# CANoPi.net
KiCad netlist of a schematic drawn in EAGLE
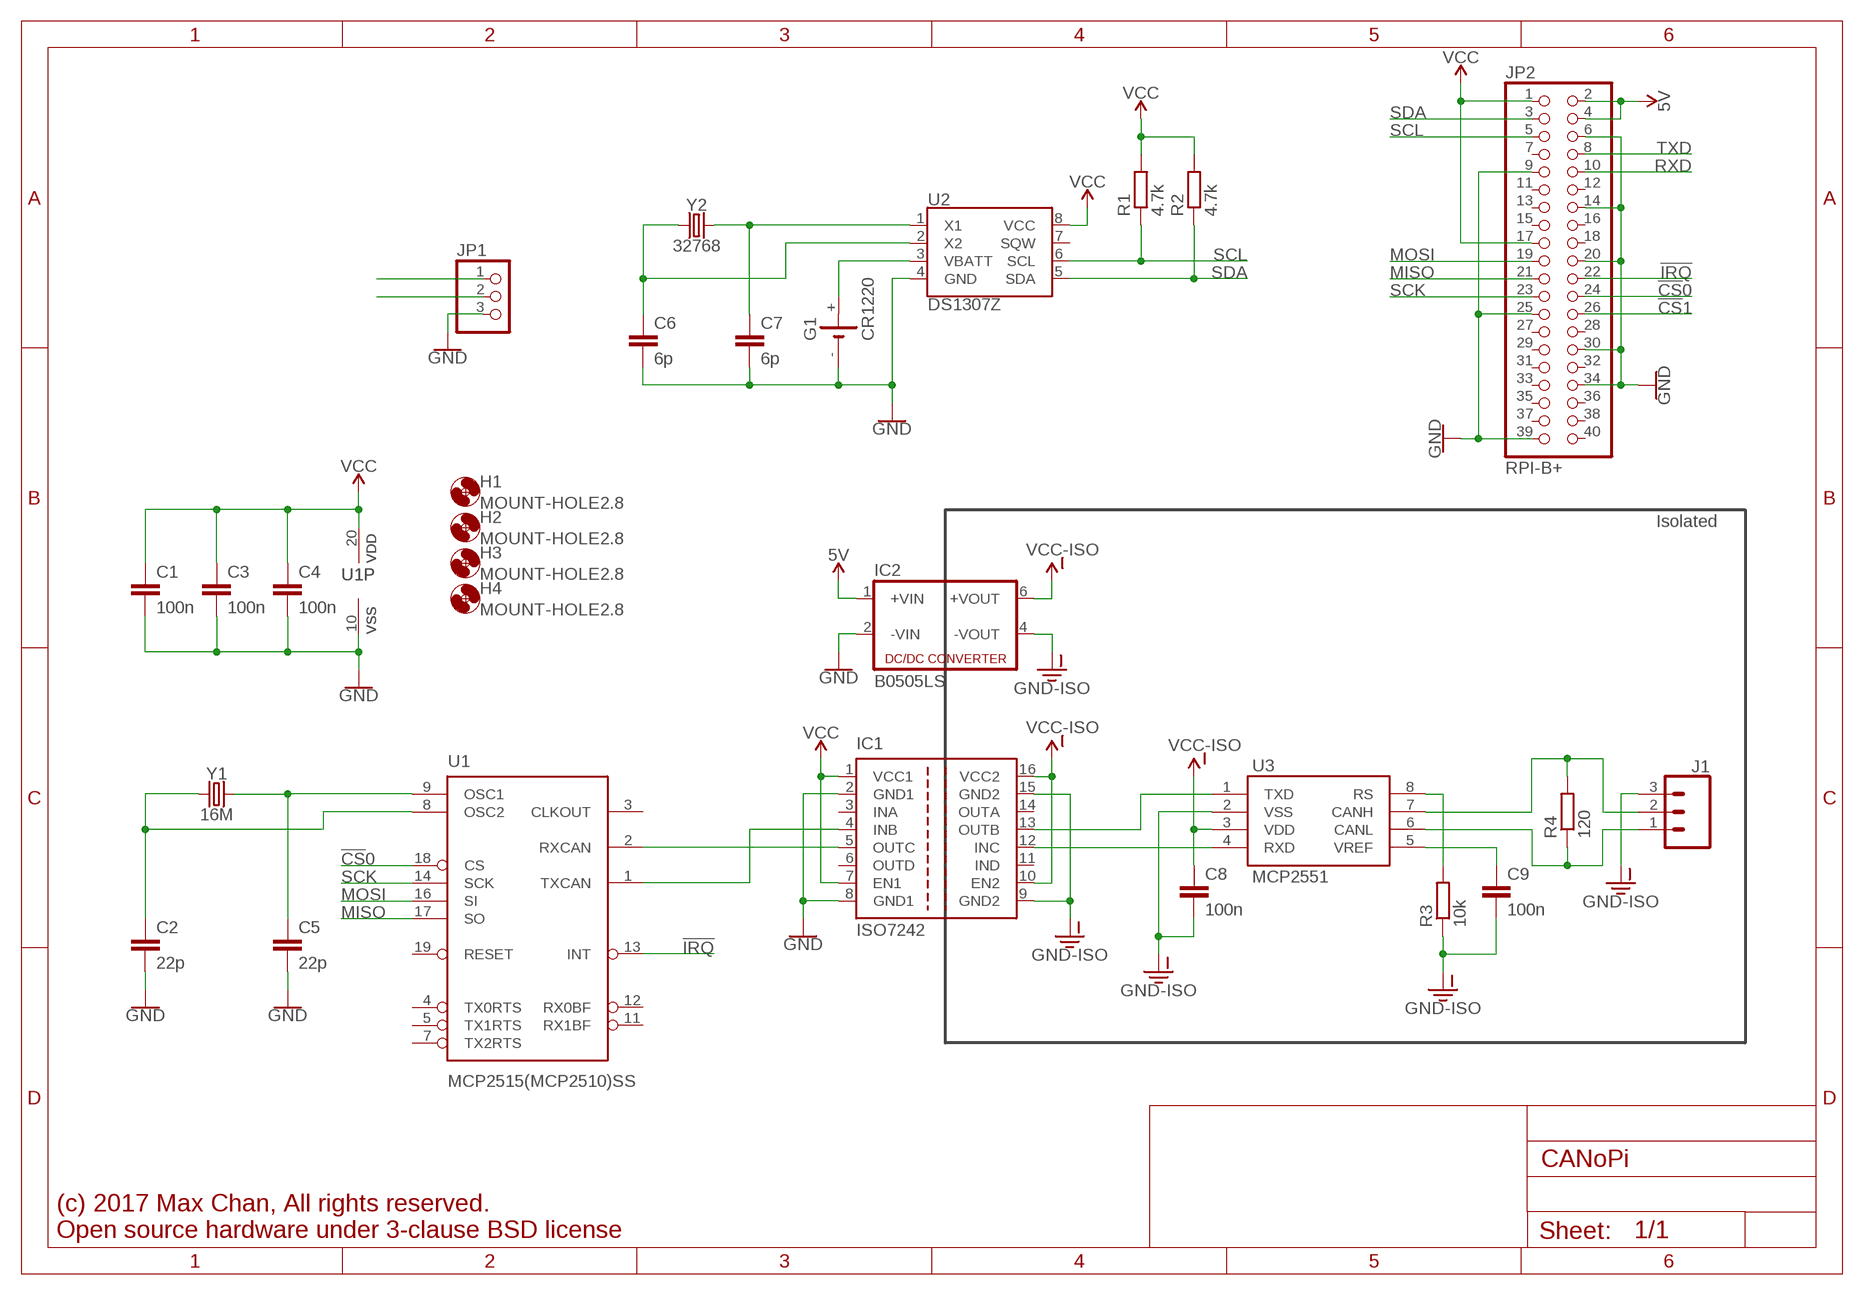
[diagram p0: schematic, sheet 1]

(export (version "E")
  (design (tool "Eeschema 10.0.6"))
  (components
    (comp (ref "C1")
      (value "100n")
      (footprint "eagle-import:C0603")
      (libsource (lib "eagle-import") (part "C-EUC0603"))
    )
    (comp (ref "C2")
      (value "22p")
      (footprint "eagle-import:C0603")
      (libsource (lib "eagle-import") (part "C-EUC0603"))
    )
    (comp (ref "C3")
      (value "100n")
      (footprint "eagle-import:C0603")
      (libsource (lib "eagle-import") (part "C-EUC0603"))
    )
    (comp (ref "C4")
      (value "100n")
      (footprint "eagle-import:C0603")
      (libsource (lib "eagle-import") (part "C-EUC0603"))
    )
    (comp (ref "C5")
      (value "22p")
      (footprint "eagle-import:C0603")
      (libsource (lib "eagle-import") (part "C-EUC0603"))
    )
    (comp (ref "C6")
      (value "6p")
      (footprint "eagle-import:C0603")
      (libsource (lib "eagle-import") (part "C-EUC0603"))
    )
    (comp (ref "C7")
      (value "6p")
      (footprint "eagle-import:C0603")
      (libsource (lib "eagle-import") (part "C-EUC0603"))
    )
    (comp (ref "C8")
      (value "100n")
      (footprint "eagle-import:C0603")
      (libsource (lib "eagle-import") (part "C-EUC0603"))
    )
    (comp (ref "C9")
      (value "100n")
      (footprint "eagle-import:C0603")
      (libsource (lib "eagle-import") (part "C-EUC0603"))
    )
    (comp (ref "G1")
      (value "CR1220")
      (footprint "eagle-import:CH291-1220LF")
      (libsource (lib "eagle-import") (part "CH291-1220LF"))
    )
    (comp (ref "H1")
      (value "MOUNT-HOLE2.8")
      (footprint "eagle-import:2,8")
      (libsource (lib "eagle-import") (part "MOUNT-HOLE2.8"))
    )
    (comp (ref "H2")
      (value "MOUNT-HOLE2.8")
      (footprint "eagle-import:2,8")
      (libsource (lib "eagle-import") (part "MOUNT-HOLE2.8"))
    )
    (comp (ref "H3")
      (value "MOUNT-HOLE2.8")
      (footprint "eagle-import:2,8")
      (libsource (lib "eagle-import") (part "MOUNT-HOLE2.8"))
    )
    (comp (ref "H4")
      (value "MOUNT-HOLE2.8")
      (footprint "eagle-import:2,8")
      (libsource (lib "eagle-import") (part "MOUNT-HOLE2.8"))
    )
    (comp (ref "IC1")
      (value "ISO7242")
      (footprint "eagle-import:SO-16DW")
      (fields (field (name "MPN") "ISO7242MDW"))
      (libsource (lib "eagle-import") (part "ISO7242"))
    )
    (comp (ref "IC2")
      (value "B0505LS")
      (footprint "eagle-import:NMA-SINGLE")
      (libsource (lib "eagle-import") (part "NMA-SINGLE"))
    )
    (comp (ref "J1")
      (value "CONN_03SCREW")
      (footprint "eagle-import:SCREWTERMINAL-3.5MM-3")
      (libsource (lib "eagle-import") (part "CONN_03SCREW"))
    )
    (comp (ref "JP1")
      (value "PINHD-1X3/90")
      (footprint "eagle-import:1X03_90")
      (libsource (lib "eagle-import") (part "PINHD-1X3/90"))
    )
    (comp (ref "JP2")
      (value "RPI-B+")
      (footprint "eagle-import:2X20")
      (libsource (lib "eagle-import") (part "PINHD-2X20"))
    )
    (comp (ref "R1")
      (value "4.7k")
      (footprint "eagle-import:R0603")
      (libsource (lib "eagle-import") (part "R-EU_R0603"))
    )
    (comp (ref "R2")
      (value "4.7k")
      (footprint "eagle-import:R0603")
      (libsource (lib "eagle-import") (part "R-EU_R0603"))
    )
    (comp (ref "R3")
      (value "10k")
      (footprint "eagle-import:R0603")
      (libsource (lib "eagle-import") (part "R-EU_R0603"))
    )
    (comp (ref "R4")
      (value "120")
      (footprint "eagle-import:R0603")
      (libsource (lib "eagle-import") (part "R-EU_R0603"))
    )
    (comp (ref "U1")
      (value "MCP2515(MCP2510)SS")
      (footprint "eagle-import:SSOP20")
      (libsource (lib "eagle-import") (part "MCP2515(MCP2510)SS"))
    )
    (comp (ref "U2")
      (value "DS1307Z")
      (footprint "eagle-import:SO08-0.15")
      (libsource (lib "eagle-import") (part "DS1307Z"))
    )
    (comp (ref "U3")
      (value "MCP2551")
      (footprint "eagle-import:SO08")
      (libsource (lib "eagle-import") (part "MCP2551"))
    )
    (comp (ref "Y1")
      (value "16M")
      (footprint "eagle-import:CRYSTAL-SMD-5X3.2-4PAD")
      (libsource (lib "eagle-import") (part "CRYSTALSMD-5X3.2-4PAD"))
    )
    (comp (ref "Y2")
      (value "32768")
      (footprint "eagle-import:CRYSTAL-SMD-3.2X1.5MM")
      (libsource (lib "eagle-import") (part "CRYSTALSMD-3.2X1.5"))
    )
  )
  (nets
    (net (code "1") (name "/MISO") (class "Default")
      (node (ref "JP2") (pin "21") (pinfunction "21_21") (pintype "passive"))
      (node (ref "U1") (pin "17") (pinfunction "SO_17") (pintype "output"))
    )
    (net (code "2") (name "/MOSI") (class "Default")
      (node (ref "JP2") (pin "19") (pinfunction "19_19") (pintype "passive"))
      (node (ref "U1") (pin "16") (pinfunction "SI_16") (pintype "input"))
    )
    (net (code "3") (name "/RXD") (class "Default")
      (node (ref "JP1") (pin "1") (pinfunction "1_1") (pintype "passive"))
      (node (ref "JP2") (pin "10") (pinfunction "10_10") (pintype "passive"))
    )
    (net (code "4") (name "/SCK") (class "Default")
      (node (ref "JP2") (pin "23") (pinfunction "23_23") (pintype "passive"))
      (node (ref "U1") (pin "14") (pinfunction "SCK_14") (pintype "input"))
    )
    (net (code "5") (name "/SCL") (class "Default")
      (node (ref "JP2") (pin "5") (pinfunction "5_5") (pintype "passive"))
      (node (ref "R1") (pin "1") (pinfunction "1_1") (pintype "passive"))
      (node (ref "U2") (pin "6") (pinfunction "SCL_6") (pintype "bidirectional"))
    )
    (net (code "6") (name "/SDA") (class "Default")
      (node (ref "JP2") (pin "3") (pinfunction "3_3") (pintype "passive"))
      (node (ref "R2") (pin "1") (pinfunction "1_1") (pintype "passive"))
      (node (ref "U2") (pin "5") (pinfunction "SDA_5") (pintype "bidirectional"))
    )
    (net (code "7") (name "/TXD") (class "Default")
      (node (ref "JP1") (pin "2") (pinfunction "2_2") (pintype "passive"))
      (node (ref "JP2") (pin "8") (pinfunction "8_8") (pintype "passive"))
    )
    (net (code "8") (name "/~{CS}0") (class "Default")
      (node (ref "JP2") (pin "24") (pinfunction "24_24") (pintype "passive"))
      (node (ref "U1") (pin "18") (pinfunction "CS_18") (pintype "input"))
    )
    (net (code "9") (name "/~{CS}1") (class "Default")
      (node (ref "JP2") (pin "26") (pinfunction "26_26") (pintype "passive"))
    )
    (net (code "10") (name "/~{IRQ}") (class "Default")
      (node (ref "JP2") (pin "22") (pinfunction "22_22") (pintype "passive"))
      (node (ref "U1") (pin "13") (pinfunction "INT_13") (pintype "output"))
    )
    (net (code "11") (name "5V") (class "Default")
      (node (ref "IC2") (pin "1") (pinfunction "+VIN_1") (pintype "passive"))
      (node (ref "JP2") (pin "2") (pinfunction "2_2") (pintype "passive"))
      (node (ref "JP2") (pin "4") (pinfunction "4_4") (pintype "passive"))
    )
    (net (code "12") (name "GND") (class "Default")
      (node (ref "C1") (pin "2") (pinfunction "2_2") (pintype "passive"))
      (node (ref "C2") (pin "2") (pinfunction "2_2") (pintype "passive"))
      (node (ref "C3") (pin "2") (pinfunction "2_2") (pintype "passive"))
      (node (ref "C4") (pin "2") (pinfunction "2_2") (pintype "passive"))
      (node (ref "C5") (pin "2") (pinfunction "2_2") (pintype "passive"))
      (node (ref "C6") (pin "2") (pinfunction "2_2") (pintype "passive"))
      (node (ref "C7") (pin "2") (pinfunction "2_2") (pintype "passive"))
      (node (ref "G1") (pin "-") (pinfunction "-_-") (pintype "passive"))
      (node (ref "IC1") (pin "2") (pinfunction "GND1_2") (pintype "power_in"))
      (node (ref "IC1") (pin "8") (pinfunction "GND1_8") (pintype "power_in"))
      (node (ref "IC2") (pin "2") (pinfunction "-VIN_2") (pintype "passive"))
      (node (ref "JP1") (pin "3") (pinfunction "3_3") (pintype "passive"))
      (node (ref "JP2") (pin "14") (pinfunction "14_14") (pintype "passive"))
      (node (ref "JP2") (pin "20") (pinfunction "20_20") (pintype "passive"))
      (node (ref "JP2") (pin "25") (pinfunction "25_25") (pintype "passive"))
      (node (ref "JP2") (pin "30") (pinfunction "30_30") (pintype "passive"))
      (node (ref "JP2") (pin "34") (pinfunction "34_34") (pintype "passive"))
      (node (ref "JP2") (pin "39") (pinfunction "39_39") (pintype "passive"))
      (node (ref "JP2") (pin "6") (pinfunction "6_6") (pintype "passive"))
      (node (ref "JP2") (pin "9") (pinfunction "9_9") (pintype "passive"))
      (node (ref "U1") (pin "10") (pinfunction "VSS_10") (pintype "power_in"))
      (node (ref "U2") (pin "4") (pinfunction "GND_4") (pintype "bidirectional"))
    )
    (net (code "13") (name "GND-ISO") (class "Default")
      (node (ref "C8") (pin "2") (pinfunction "2_2") (pintype "passive"))
      (node (ref "C9") (pin "2") (pinfunction "2_2") (pintype "passive"))
      (node (ref "IC1") (pin "15") (pinfunction "GND2_15") (pintype "power_in"))
      (node (ref "IC1") (pin "9") (pinfunction "GND2_9") (pintype "power_in"))
      (node (ref "IC2") (pin "4") (pinfunction "-VOUT_4") (pintype "passive"))
      (node (ref "J1") (pin "3") (pinfunction "3_3") (pintype "passive"))
      (node (ref "R3") (pin "1") (pinfunction "1_1") (pintype "passive"))
      (node (ref "U3") (pin "2") (pinfunction "VSS_2") (pintype "bidirectional"))
    )
    (net (code "14") (name "Net-(IC1-INB)") (class "Default")
      (node (ref "IC1") (pin "4") (pinfunction "INB_4") (pintype "input"))
      (node (ref "U1") (pin "1") (pinfunction "TXCAN_1") (pintype "output"))
    )
    (net (code "15") (name "Net-(IC1-INC)") (class "Default")
      (node (ref "IC1") (pin "12") (pinfunction "INC_12") (pintype "input"))
      (node (ref "U3") (pin "4") (pinfunction "RXD_4") (pintype "bidirectional"))
    )
    (net (code "16") (name "Net-(IC1-OUTB)") (class "Default")
      (node (ref "IC1") (pin "13") (pinfunction "OUTB_13") (pintype "output"))
      (node (ref "U3") (pin "1") (pinfunction "TXD_1") (pintype "bidirectional"))
    )
    (net (code "17") (name "Net-(IC1-OUTC)") (class "Default")
      (node (ref "IC1") (pin "5") (pinfunction "OUTC_5") (pintype "output"))
      (node (ref "U1") (pin "2") (pinfunction "RXCAN_2") (pintype "input"))
    )
    (net (code "18") (name "Net-(U1A-OSC1)") (class "Default")
      (node (ref "C5") (pin "1") (pinfunction "1_1") (pintype "passive"))
      (node (ref "U1") (pin "9") (pinfunction "OSC1_9") (pintype "input"))
      (node (ref "Y1") (pin "3") (pinfunction "2_3") (pintype "passive"))
    )
    (net (code "19") (name "Net-(U1A-OSC2)") (class "Default")
      (node (ref "C2") (pin "1") (pinfunction "1_1") (pintype "passive"))
      (node (ref "U1") (pin "8") (pinfunction "OSC2_8") (pintype "output"))
      (node (ref "Y1") (pin "1") (pinfunction "1_1") (pintype "passive"))
    )
    (net (code "20") (name "Net-(U2-VBATT)") (class "Default")
      (node (ref "G1") (pin "+") (pinfunction "+_+") (pintype "passive"))
      (node (ref "U2") (pin "3") (pinfunction "VBATT_3") (pintype "bidirectional"))
    )
    (net (code "21") (name "Net-(U2-X1)") (class "Default")
      (node (ref "C7") (pin "1") (pinfunction "1_1") (pintype "passive"))
      (node (ref "U2") (pin "1") (pinfunction "X1_1") (pintype "bidirectional"))
      (node (ref "Y2") (pin "P$2") (pinfunction "2_P$2") (pintype "passive"))
    )
    (net (code "22") (name "Net-(U2-X2)") (class "Default")
      (node (ref "C6") (pin "1") (pinfunction "1_1") (pintype "passive"))
      (node (ref "U2") (pin "2") (pinfunction "X2_2") (pintype "bidirectional"))
      (node (ref "Y2") (pin "P$1") (pinfunction "1_P$1") (pintype "passive"))
    )
    (net (code "23") (name "Net-(U3-CANH)") (class "Default")
      (node (ref "J1") (pin "2") (pinfunction "2_2") (pintype "passive"))
      (node (ref "R4") (pin "2") (pinfunction "2_2") (pintype "passive"))
      (node (ref "U3") (pin "7") (pinfunction "CANH_7") (pintype "bidirectional"))
    )
    (net (code "24") (name "Net-(U3-CANL)") (class "Default")
      (node (ref "J1") (pin "1") (pinfunction "1_1") (pintype "passive"))
      (node (ref "R4") (pin "1") (pinfunction "1_1") (pintype "passive"))
      (node (ref "U3") (pin "6") (pinfunction "CANL_6") (pintype "bidirectional"))
    )
    (net (code "25") (name "Net-(U3-RS)") (class "Default")
      (node (ref "R3") (pin "2") (pinfunction "2_2") (pintype "passive"))
      (node (ref "U3") (pin "8") (pinfunction "RS_8") (pintype "bidirectional"))
    )
    (net (code "26") (name "Net-(U3-VREF)") (class "Default")
      (node (ref "C9") (pin "1") (pinfunction "1_1") (pintype "passive"))
      (node (ref "U3") (pin "5") (pinfunction "VREF_5") (pintype "bidirectional"))
    )
    (net (code "27") (name "VCC") (class "Default")
      (node (ref "C1") (pin "1") (pinfunction "1_1") (pintype "passive"))
      (node (ref "C3") (pin "1") (pinfunction "1_1") (pintype "passive"))
      (node (ref "C4") (pin "1") (pinfunction "1_1") (pintype "passive"))
      (node (ref "IC1") (pin "1") (pinfunction "VCC1_1") (pintype "power_in"))
      (node (ref "IC1") (pin "7") (pinfunction "EN1_7") (pintype "input"))
      (node (ref "JP2") (pin "1") (pinfunction "1_1") (pintype "passive"))
      (node (ref "JP2") (pin "17") (pinfunction "17_17") (pintype "passive"))
      (node (ref "R1") (pin "2") (pinfunction "2_2") (pintype "passive"))
      (node (ref "R2") (pin "2") (pinfunction "2_2") (pintype "passive"))
      (node (ref "U1") (pin "20") (pinfunction "VDD_20") (pintype "power_in"))
      (node (ref "U2") (pin "8") (pinfunction "VCC_8") (pintype "bidirectional"))
    )
    (net (code "28") (name "VCC-ISO") (class "Default")
      (node (ref "C8") (pin "1") (pinfunction "1_1") (pintype "passive"))
      (node (ref "IC1") (pin "10") (pinfunction "EN2_10") (pintype "input"))
      (node (ref "IC1") (pin "16") (pinfunction "VCC2_16") (pintype "power_in"))
      (node (ref "IC2") (pin "6") (pinfunction "+VOUT_6") (pintype "passive"))
      (node (ref "U3") (pin "3") (pinfunction "VDD_3") (pintype "bidirectional"))
    )
    (net (code "29") (name "unconnected-(IC1-INA-Pad3)") (class "Default")
      (node (ref "IC1") (pin "3") (pinfunction "INA_3") (pintype "input"))
    )
    (net (code "30") (name "unconnected-(IC1-IND-Pad11)") (class "Default")
      (node (ref "IC1") (pin "11") (pinfunction "IND_11") (pintype "input"))
    )
    (net (code "31") (name "unconnected-(IC1-OUTA-Pad14)") (class "Default")
      (node (ref "IC1") (pin "14") (pinfunction "OUTA_14") (pintype "output"))
    )
    (net (code "32") (name "unconnected-(IC1-OUTD-Pad6)") (class "Default")
      (node (ref "IC1") (pin "6") (pinfunction "OUTD_6") (pintype "output"))
    )
    (net (code "33") (name "unconnected-(JP2-Pad7)") (class "Default")
      (node (ref "JP2") (pin "7") (pinfunction "7_7") (pintype "passive"))
    )
    (net (code "34") (name "unconnected-(JP2-Pad11)") (class "Default")
      (node (ref "JP2") (pin "11") (pinfunction "11_11") (pintype "passive"))
    )
    (net (code "35") (name "unconnected-(JP2-Pad12)") (class "Default")
      (node (ref "JP2") (pin "12") (pinfunction "12_12") (pintype "passive"))
    )
    (net (code "36") (name "unconnected-(JP2-Pad13)") (class "Default")
      (node (ref "JP2") (pin "13") (pinfunction "13_13") (pintype "passive"))
    )
    (net (code "37") (name "unconnected-(JP2-Pad15)") (class "Default")
      (node (ref "JP2") (pin "15") (pinfunction "15_15") (pintype "passive"))
    )
    (net (code "38") (name "unconnected-(JP2-Pad16)") (class "Default")
      (node (ref "JP2") (pin "16") (pinfunction "16_16") (pintype "passive"))
    )
    (net (code "39") (name "unconnected-(JP2-Pad18)") (class "Default")
      (node (ref "JP2") (pin "18") (pinfunction "18_18") (pintype "passive"))
    )
    (net (code "40") (name "unconnected-(JP2-Pad27)") (class "Default")
      (node (ref "JP2") (pin "27") (pinfunction "27_27") (pintype "passive"))
    )
    (net (code "41") (name "unconnected-(JP2-Pad28)") (class "Default")
      (node (ref "JP2") (pin "28") (pinfunction "28_28") (pintype "passive"))
    )
    (net (code "42") (name "unconnected-(JP2-Pad29)") (class "Default")
      (node (ref "JP2") (pin "29") (pinfunction "29_29") (pintype "passive"))
    )
    (net (code "43") (name "unconnected-(JP2-Pad31)") (class "Default")
      (node (ref "JP2") (pin "31") (pinfunction "31_31") (pintype "passive"))
    )
    (net (code "44") (name "unconnected-(JP2-Pad32)") (class "Default")
      (node (ref "JP2") (pin "32") (pinfunction "32_32") (pintype "passive"))
    )
    (net (code "45") (name "unconnected-(JP2-Pad33)") (class "Default")
      (node (ref "JP2") (pin "33") (pinfunction "33_33") (pintype "passive"))
    )
    (net (code "46") (name "unconnected-(JP2-Pad35)") (class "Default")
      (node (ref "JP2") (pin "35") (pinfunction "35_35") (pintype "passive"))
    )
    (net (code "47") (name "unconnected-(JP2-Pad36)") (class "Default")
      (node (ref "JP2") (pin "36") (pinfunction "36_36") (pintype "passive"))
    )
    (net (code "48") (name "unconnected-(JP2-Pad37)") (class "Default")
      (node (ref "JP2") (pin "37") (pinfunction "37_37") (pintype "passive"))
    )
    (net (code "49") (name "unconnected-(JP2-Pad38)") (class "Default")
      (node (ref "JP2") (pin "38") (pinfunction "38_38") (pintype "passive"))
    )
    (net (code "50") (name "unconnected-(JP2-Pad40)") (class "Default")
      (node (ref "JP2") (pin "40") (pinfunction "40_40") (pintype "passive"))
    )
    (net (code "51") (name "unconnected-(U1A-CLKOUT-Pad3)") (class "Default")
      (node (ref "U1") (pin "3") (pinfunction "CLKOUT_3") (pintype "output"))
    )
    (net (code "52") (name "unconnected-(U1A-RESET-Pad19)") (class "Default")
      (node (ref "U1") (pin "19") (pinfunction "RESET_19") (pintype "input"))
    )
    (net (code "53") (name "unconnected-(U1A-RX0BF-Pad12)") (class "Default")
      (node (ref "U1") (pin "12") (pinfunction "RX0BF_12") (pintype "output"))
    )
    (net (code "54") (name "unconnected-(U1A-RX1BF-Pad11)") (class "Default")
      (node (ref "U1") (pin "11") (pinfunction "RX1BF_11") (pintype "output"))
    )
    (net (code "55") (name "unconnected-(U1A-TX0RTS-Pad4)") (class "Default")
      (node (ref "U1") (pin "4") (pinfunction "TX0RTS_4") (pintype "input"))
    )
    (net (code "56") (name "unconnected-(U1A-TX1RTS-Pad5)") (class "Default")
      (node (ref "U1") (pin "5") (pinfunction "TX1RTS_5") (pintype "input"))
    )
    (net (code "57") (name "unconnected-(U1A-TX2RTS-Pad7)") (class "Default")
      (node (ref "U1") (pin "7") (pinfunction "TX2RTS_7") (pintype "input"))
    )
    (net (code "58") (name "unconnected-(U2-SQW-Pad7)") (class "Default")
      (node (ref "U2") (pin "7") (pinfunction "SQW_7") (pintype "bidirectional"))
    )
  )
)
